# fabmoney.net
KiCad netlist of a schematic drawn in EAGLE
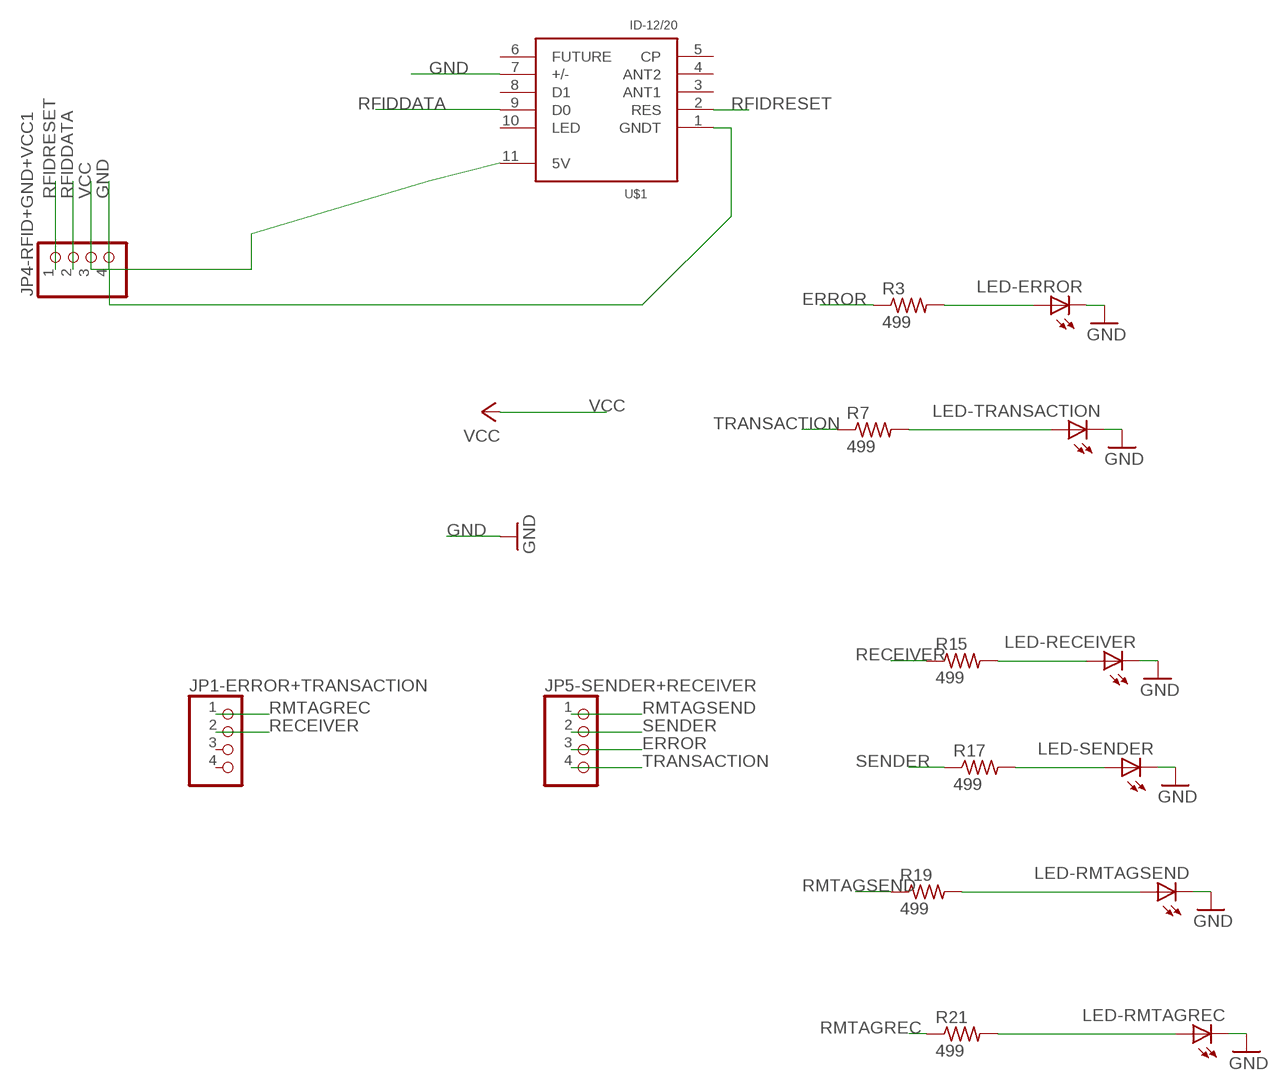
[diagram p0: schematic, sheet 1]

(export (version "E")
  (design (tool "Eeschema 10.0.6"))
  (components
    (comp (ref "JP1-ERROR+TRANSACTION")
      (value "PINHD-1X4")
      (footprint "eagle-import:1X04")
      (libsource (lib "eagle-import") (part "PINHD-1X4"))
    )
    (comp (ref "JP4-RFID+GND+VCC1")
      (value "PINHD-1X4")
      (footprint "eagle-import:1X04")
      (libsource (lib "eagle-import") (part "PINHD-1X4"))
    )
    (comp (ref "JP5-SENDER+RECEIVER")
      (value "PINHD-1X4")
      (footprint "eagle-import:1X04")
      (libsource (lib "eagle-import") (part "PINHD-1X4"))
    )
    (comp (ref "LED-ERROR")
      (value "LED5MM")
      (footprint "eagle-import:LED5MM")
      (libsource (lib "eagle-import") (part "LED5MM"))
    )
    (comp (ref "LED-RECEIVER")
      (value "LED5MM")
      (footprint "eagle-import:LED5MM")
      (libsource (lib "eagle-import") (part "LED5MM"))
    )
    (comp (ref "LED-RMTAGREC")
      (value "LED5MM")
      (footprint "eagle-import:LED5MM")
      (libsource (lib "eagle-import") (part "LED5MM"))
    )
    (comp (ref "LED-RMTAGSEND")
      (value "LED5MM")
      (footprint "eagle-import:LED5MM")
      (libsource (lib "eagle-import") (part "LED5MM"))
    )
    (comp (ref "LED-SENDER")
      (value "LED5MM")
      (footprint "eagle-import:LED5MM")
      (libsource (lib "eagle-import") (part "LED5MM"))
    )
    (comp (ref "LED-TRANSACTION")
      (value "LED5MM")
      (footprint "eagle-import:LED5MM")
      (libsource (lib "eagle-import") (part "LED5MM"))
    )
    (comp (ref "R3")
      (value "499")
      (footprint "eagle-import:1206")
      (libsource (lib "eagle-import") (part "RESISTOR1206"))
    )
    (comp (ref "R7")
      (value "499")
      (footprint "eagle-import:1206")
      (libsource (lib "eagle-import") (part "RESISTOR1206"))
    )
    (comp (ref "R15")
      (value "499")
      (footprint "eagle-import:1206")
      (libsource (lib "eagle-import") (part "RESISTOR1206"))
    )
    (comp (ref "R17")
      (value "499")
      (footprint "eagle-import:1206")
      (libsource (lib "eagle-import") (part "RESISTOR1206"))
    )
    (comp (ref "R19")
      (value "499")
      (footprint "eagle-import:1206")
      (libsource (lib "eagle-import") (part "RESISTOR1206"))
    )
    (comp (ref "R21")
      (value "499")
      (footprint "eagle-import:1206")
      (libsource (lib "eagle-import") (part "RESISTOR1206"))
    )
    (comp (ref "U$1")
      (value "ID-12/20")
      (footprint "eagle-import:ID-12")
      (libsource (lib "eagle-import") (part "ID-12/20"))
    )
  )
  (nets
    (net (code "1") (name "/ERROR") (class "Default")
      (node (ref "JP5-SENDER+RECEIVER") (pin "3") (pinfunction "3_3") (pintype "passive"))
      (node (ref "R3") (pin "1") (pinfunction "1_1") (pintype "passive"))
    )
    (net (code "2") (name "/RECEIVER") (class "Default")
      (node (ref "JP1-ERROR+TRANSACTION") (pin "2") (pinfunction "2_2") (pintype "passive"))
      (node (ref "R15") (pin "1") (pinfunction "1_1") (pintype "passive"))
    )
    (net (code "3") (name "/RFIDDATA") (class "Default")
      (node (ref "JP4-RFID+GND+VCC1") (pin "2") (pinfunction "2_2") (pintype "passive"))
      (node (ref "U$1") (pin "9") (pinfunction "D0_9") (pintype "bidirectional"))
    )
    (net (code "4") (name "/RFIDRESET") (class "Default")
      (node (ref "JP4-RFID+GND+VCC1") (pin "1") (pinfunction "1_1") (pintype "passive"))
      (node (ref "U$1") (pin "2") (pinfunction "RES_2") (pintype "bidirectional"))
    )
    (net (code "5") (name "/RMTAGREC") (class "Default")
      (node (ref "JP1-ERROR+TRANSACTION") (pin "1") (pinfunction "1_1") (pintype "passive"))
      (node (ref "R21") (pin "1") (pinfunction "1_1") (pintype "passive"))
    )
    (net (code "6") (name "/RMTAGSEND") (class "Default")
      (node (ref "JP5-SENDER+RECEIVER") (pin "1") (pinfunction "1_1") (pintype "passive"))
      (node (ref "R19") (pin "1") (pinfunction "1_1") (pintype "passive"))
    )
    (net (code "7") (name "/SENDER") (class "Default")
      (node (ref "JP5-SENDER+RECEIVER") (pin "2") (pinfunction "2_2") (pintype "passive"))
      (node (ref "R17") (pin "1") (pinfunction "1_1") (pintype "passive"))
    )
    (net (code "8") (name "/TRANSACTION") (class "Default")
      (node (ref "JP5-SENDER+RECEIVER") (pin "4") (pinfunction "4_4") (pintype "passive"))
      (node (ref "R7") (pin "1") (pinfunction "1_1") (pintype "passive"))
    )
    (net (code "9") (name "GND") (class "Default")
      (node (ref "JP4-RFID+GND+VCC1") (pin "4") (pinfunction "4_4") (pintype "passive"))
      (node (ref "LED-ERROR") (pin "K") (pinfunction "C_K") (pintype "passive"))
      (node (ref "LED-RECEIVER") (pin "K") (pinfunction "C_K") (pintype "passive"))
      (node (ref "LED-RMTAGREC") (pin "K") (pinfunction "C_K") (pintype "passive"))
      (node (ref "LED-RMTAGSEND") (pin "K") (pinfunction "C_K") (pintype "passive"))
      (node (ref "LED-SENDER") (pin "K") (pinfunction "C_K") (pintype "passive"))
      (node (ref "LED-TRANSACTION") (pin "K") (pinfunction "C_K") (pintype "passive"))
      (node (ref "U$1") (pin "1") (pinfunction "GNDT_1") (pintype "bidirectional"))
      (node (ref "U$1") (pin "7") (pinfunction "+/-_7") (pintype "bidirectional"))
    )
    (net (code "10") (name "Net-(LED-ERROR-PadA)") (class "Default")
      (node (ref "LED-ERROR") (pin "A") (pinfunction "A_A") (pintype "passive"))
      (node (ref "R3") (pin "2") (pinfunction "2_2") (pintype "passive"))
    )
    (net (code "11") (name "Net-(LED-RECEIVER-PadA)") (class "Default")
      (node (ref "LED-RECEIVER") (pin "A") (pinfunction "A_A") (pintype "passive"))
      (node (ref "R15") (pin "2") (pinfunction "2_2") (pintype "passive"))
    )
    (net (code "12") (name "Net-(LED-RMTAGREC-PadA)") (class "Default")
      (node (ref "LED-RMTAGREC") (pin "A") (pinfunction "A_A") (pintype "passive"))
      (node (ref "R21") (pin "2") (pinfunction "2_2") (pintype "passive"))
    )
    (net (code "13") (name "Net-(LED-RMTAGSEND-PadA)") (class "Default")
      (node (ref "LED-RMTAGSEND") (pin "A") (pinfunction "A_A") (pintype "passive"))
      (node (ref "R19") (pin "2") (pinfunction "2_2") (pintype "passive"))
    )
    (net (code "14") (name "Net-(LED-SENDER-PadA)") (class "Default")
      (node (ref "LED-SENDER") (pin "A") (pinfunction "A_A") (pintype "passive"))
      (node (ref "R17") (pin "2") (pinfunction "2_2") (pintype "passive"))
    )
    (net (code "15") (name "Net-(LED-TRANSACTION-PadA)") (class "Default")
      (node (ref "LED-TRANSACTION") (pin "A") (pinfunction "A_A") (pintype "passive"))
      (node (ref "R7") (pin "2") (pinfunction "2_2") (pintype "passive"))
    )
    (net (code "16") (name "VCC") (class "Default")
      (node (ref "JP4-RFID+GND+VCC1") (pin "3") (pinfunction "3_3") (pintype "passive"))
      (node (ref "U$1") (pin "11") (pinfunction "5V_11") (pintype "bidirectional"))
    )
    (net (code "17") (name "unconnected-(JP1-ERROR+TRANSACTION-Pad3)") (class "Default")
      (node (ref "JP1-ERROR+TRANSACTION") (pin "3") (pinfunction "3_3") (pintype "passive"))
    )
    (net (code "18") (name "unconnected-(JP1-ERROR+TRANSACTION-Pad4)") (class "Default")
      (node (ref "JP1-ERROR+TRANSACTION") (pin "4") (pinfunction "4_4") (pintype "passive"))
    )
    (net (code "19") (name "unconnected-(U$1-ANT1-Pad3)") (class "Default")
      (node (ref "U$1") (pin "3") (pinfunction "ANT1_3") (pintype "bidirectional"))
    )
    (net (code "20") (name "unconnected-(U$1-ANT2-Pad4)") (class "Default")
      (node (ref "U$1") (pin "4") (pinfunction "ANT2_4") (pintype "bidirectional"))
    )
    (net (code "21") (name "unconnected-(U$1-CP-Pad5)") (class "Default")
      (node (ref "U$1") (pin "5") (pinfunction "CP_5") (pintype "bidirectional"))
    )
    (net (code "22") (name "unconnected-(U$1-D1-Pad8)") (class "Default")
      (node (ref "U$1") (pin "8") (pinfunction "D1_8") (pintype "bidirectional"))
    )
    (net (code "23") (name "unconnected-(U$1-FUTURE-Pad6)") (class "Default")
      (node (ref "U$1") (pin "6") (pinfunction "FUTURE_6") (pintype "bidirectional"))
    )
    (net (code "24") (name "unconnected-(U$1-LED-Pad10)") (class "Default")
      (node (ref "U$1") (pin "10") (pinfunction "LED_10") (pintype "bidirectional"))
    )
  )
)
